# config.net
KiCad netlist of a schematic drawn in Altium Designer
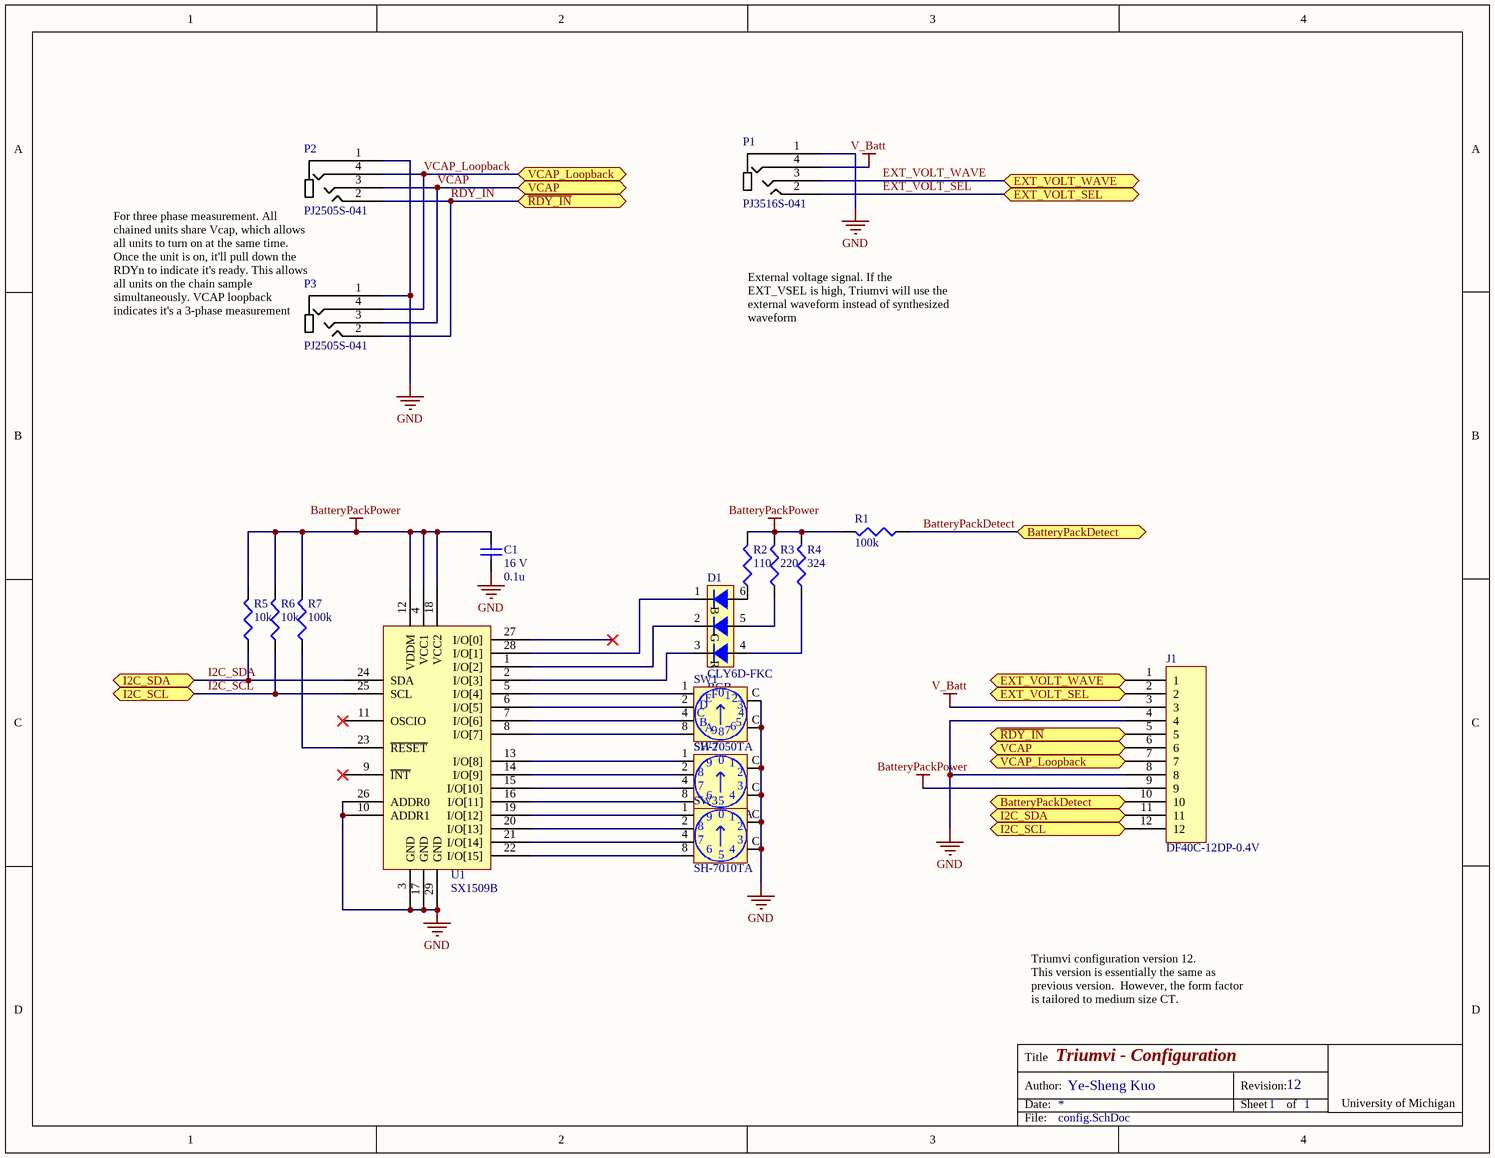
[diagram p0: config.SchDoc]

(export (version "E")
  (design (tool "Eeschema 10.0.6"))
  (components
    (comp (ref "C1")
      (value "0.1u")
      (footprint "0402")
      (description "0.10µF ±10% 16V Ceramic Capacitor X7R 0402")
      (fields
        (field (name "VOLTAGE RATED") "16 V")
        (field (name "TOLERANCE") "10%")
        (field (name "MANUFACTURER PART NUMBER") "GRM155R71C104KA88D")
      )
      (libsource (lib "capacitors") (part "GRM155R71C104KA88D"))
    )
    (comp (ref "D1")
      (value "CLY6D-FKC")
      (footprint "PLCC6")
      (fields
        (field (name "MANUFACTURER PART NUMBER") "CLY6D-FKC-CK1N1D1BB7D3D3")
        (field (name "MANUFACTURER") "CREE Inc")
        (field (name "ALTIUM_VALUE") "RGB")
      )
      (libsource (lib "LED") (part "CLY6D-FKC-CK1N1D1BB7D3D3"))
    )
    (comp (ref "J1")
      (value "DF40C-12DP-0.4V")
      (footprint "DF40C-12DP-0.4V")
      (description "Hirose BM20 Series, 0.4mm pitch, 12 pos, header")
      (libsource (lib "connectors") (part "DF40C-12DP-0.4V"))
    )
    (comp (ref "P1")
      (value "PJ3516S-041")
      (footprint "PJ3516S-041")
      (description "3.5 mm phone jack, 4 terminals")
      (libsource (lib "connectors") (part "PJ3516S-041"))
    )
    (comp (ref "P2")
      (value "PJ2505S-041")
      (footprint "PJ2505S-041")
      (description "2.5 mm phone jack, 4 terminals")
      (libsource (lib "connectors") (part "PJ2505S-041"))
    )
    (comp (ref "P3")
      (value "PJ2505S-041")
      (footprint "PJ2505S-041")
      (description "2.5 mm phone jack, 4 terminals")
      (libsource (lib "connectors") (part "PJ2505S-041"))
    )
    (comp (ref "R1")
      (value "100k")
      (footprint "0402")
      (description "RES SMD 100K OHM 1% 1/16W 0402")
      (fields (field (name "TOLERANCE") "1%") (field (name "POWER") "1/16 W"))
      (libsource (lib "resistors") (part "CRCW0402100KFKED"))
    )
    (comp (ref "R2")
      (value "110")
      (footprint "0402")
      (description "RES SMD 110 OHM 1% 1/16W 0402")
      (fields (field (name "TOLERANCE") "1%") (field (name "POWER") "1/16 W"))
      (libsource (lib "resistors") (part "CRCW0402110RFKED"))
    )
    (comp (ref "R3")
      (value "220")
      (footprint "0402")
      (description "RES SMD 220 OHM 1% 1/16W 0402")
      (fields (field (name "TOLERANCE") "1%") (field (name "POWER") "1/5 W"))
      (libsource (lib "resistors") (part "CRCW0402220RFKED"))
    )
    (comp (ref "R4")
      (value "324")
      (footprint "0402")
      (description "RES SMD 324 OHM 1% 1/16W 0402")
      (fields (field (name "TOLERANCE") "1%") (field (name "POWER") "1/16 W"))
      (libsource (lib "resistors") (part "CRCW0402324RFKED"))
    )
    (comp (ref "R5")
      (value "10k")
      (footprint "0402")
      (description "RES SMD 10K OHM 1% 1/16W 0402")
      (fields (field (name "TOLERANCE") "1%") (field (name "POWER") "1/16 W"))
      (libsource (lib "resistors") (part "CRCW040210K0FKED"))
    )
    (comp (ref "R6")
      (value "10k")
      (footprint "0402")
      (description "RES SMD 10K OHM 1% 1/16W 0402")
      (fields (field (name "TOLERANCE") "1%") (field (name "POWER") "1/16 W"))
      (libsource (lib "resistors") (part "CRCW040210K0FKED"))
    )
    (comp (ref "R7")
      (value "100k")
      (footprint "0402")
      (description "RES SMD 100K OHM 1% 1/16W 0402")
      (fields (field (name "TOLERANCE") "1%") (field (name "POWER") "1/16 W"))
      (libsource (lib "resistors") (part "CRCW0402100KFKED"))
    )
    (comp (ref "SW1")
      (value "SH-7050TA")
      (footprint "SH-7050A")
      (description "ROTARY CODED SWITCHES")
      (libsource (lib "switches") (part "SH-7050TA"))
    )
    (comp (ref "SW2")
      (value "SH-7010TA")
      (footprint "SH-7010A")
      (description "ROTARY CODED SWITCHES")
      (libsource (lib "switches") (part "SH-7010TA"))
    )
    (comp (ref "SW3")
      (value "SH-7010TA")
      (footprint "SH-7010A")
      (description "ROTARY CODED SWITCHES")
      (libsource (lib "switches") (part "SH-7010TA"))
    )
    (comp (ref "U1")
      (value "SX1509B")
      (footprint "QFN40P400X400X60_HS-29N")
      (description "Voltage Level Shifting GPIO  with LED Driver and Keypad Engine")
      (libsource (lib "io expander") (part "SX1509B"))
    )
  )
  (nets
    (net (code "1") (name "/BatteryPackDetect") (class "Default")
      (node (ref "J1") (pin "10") (pinfunction "10_10") (pintype "passive"))
      (node (ref "R1") (pin "2") (pintype "passive"))
    )
    (net (code "2") (name "/EXT_VOLT_SEL") (class "Default")
      (node (ref "J1") (pin "2") (pinfunction "2_2") (pintype "passive"))
      (node (ref "P1") (pin "2") (pinfunction "2_2") (pintype "passive"))
    )
    (net (code "3") (name "/EXT_VOLT_WAVE") (class "Default")
      (node (ref "J1") (pin "1") (pinfunction "1_1") (pintype "passive"))
      (node (ref "P1") (pin "3") (pinfunction "3_3") (pintype "passive"))
    )
    (net (code "4") (name "/I2C_SCL") (class "Default")
      (node (ref "J1") (pin "12") (pinfunction "12_12") (pintype "passive"))
      (node (ref "R6") (pin "2") (pintype "passive"))
      (node (ref "U1") (pin "25") (pinfunction "SCL_25") (pintype "passive"))
    )
    (net (code "5") (name "/I2C_SDA") (class "Default")
      (node (ref "J1") (pin "11") (pinfunction "11_11") (pintype "passive"))
      (node (ref "R5") (pin "2") (pintype "passive"))
      (node (ref "U1") (pin "24") (pinfunction "SDA_24") (pintype "passive"))
    )
    (net (code "6") (name "/VCAP") (class "Default")
      (node (ref "J1") (pin "6") (pinfunction "6_6") (pintype "passive"))
      (node (ref "P2") (pin "3") (pinfunction "3_3") (pintype "passive"))
      (node (ref "P3") (pin "3") (pinfunction "3_3") (pintype "passive"))
    )
    (net (code "7") (name "/VCAP_Loopback") (class "Default")
      (node (ref "J1") (pin "7") (pinfunction "7_7") (pintype "passive"))
      (node (ref "P2") (pin "4") (pinfunction "4_4") (pintype "passive"))
      (node (ref "P3") (pin "4") (pinfunction "4_4") (pintype "passive"))
    )
    (net (code "8") (name "/~{RDY_IN}") (class "Default")
      (node (ref "J1") (pin "5") (pinfunction "5_5") (pintype "passive"))
      (node (ref "P2") (pin "2") (pinfunction "2_2") (pintype "passive"))
      (node (ref "P3") (pin "2") (pinfunction "2_2") (pintype "passive"))
    )
    (net (code "9") (name "BatteryPackPower") (class "Default")
      (node (ref "C1") (pin "1") (pintype "passive"))
      (node (ref "J1") (pin "9") (pinfunction "9_9") (pintype "passive"))
      (node (ref "R1") (pin "1") (pintype "passive"))
      (node (ref "R2") (pin "1") (pintype "passive"))
      (node (ref "R3") (pin "1") (pintype "passive"))
      (node (ref "R4") (pin "1") (pintype "passive"))
      (node (ref "R5") (pin "1") (pintype "passive"))
      (node (ref "R6") (pin "1") (pintype "passive"))
      (node (ref "R7") (pin "1") (pintype "passive"))
      (node (ref "U1") (pin "12") (pinfunction "VDDM_12") (pintype "passive"))
      (node (ref "U1") (pin "18") (pinfunction "VCC2_18") (pintype "passive"))
      (node (ref "U1") (pin "4") (pinfunction "VCC1_4") (pintype "passive"))
    )
    (net (code "10") (name "GND") (class "Default")
      (node (ref "C1") (pin "2") (pintype "passive"))
      (node (ref "J1") (pin "4") (pinfunction "4_4") (pintype "passive"))
      (node (ref "J1") (pin "8") (pinfunction "8_8") (pintype "passive"))
      (node (ref "P1") (pin "1") (pinfunction "1_1") (pintype "passive"))
      (node (ref "P2") (pin "1") (pinfunction "1_1") (pintype "passive"))
      (node (ref "P3") (pin "1") (pinfunction "1_1") (pintype "passive"))
      (node (ref "SW1") (pin "C") (pinfunction "C_C") (pintype "passive"))
      (node (ref "SW2") (pin "C") (pinfunction "C_C") (pintype "passive"))
      (node (ref "SW3") (pin "C") (pinfunction "C_C") (pintype "passive"))
      (node (ref "U1") (pin "10") (pinfunction "ADDR1_10") (pintype "passive"))
      (node (ref "U1") (pin "17") (pinfunction "GND_17") (pintype "passive"))
      (node (ref "U1") (pin "26") (pinfunction "ADDR0_26") (pintype "passive"))
      (node (ref "U1") (pin "29") (pinfunction "GND_29") (pintype "passive"))
      (node (ref "U1") (pin "3") (pinfunction "GND_3") (pintype "passive"))
    )
    (net (code "11") (name "Net-(D1-Pad4)") (class "Default")
      (node (ref "D1") (pin "4") (pinfunction "4_4") (pintype "passive"))
      (node (ref "R4") (pin "2") (pintype "passive"))
    )
    (net (code "12") (name "Net-(D1-Pad5)") (class "Default")
      (node (ref "D1") (pin "5") (pinfunction "5_5") (pintype "passive"))
      (node (ref "R3") (pin "2") (pintype "passive"))
    )
    (net (code "13") (name "Net-(D1-Pad6)") (class "Default")
      (node (ref "D1") (pin "6") (pinfunction "6_6") (pintype "passive"))
      (node (ref "R2") (pin "2") (pintype "passive"))
    )
    (net (code "14") (name "Net-(U1-I{slash}O[1])") (class "Default")
      (node (ref "D1") (pin "1") (pintype "passive"))
      (node (ref "U1") (pin "28") (pinfunction "I/O[1]_28") (pintype "passive"))
    )
    (net (code "15") (name "Net-(U1-I{slash}O[2])") (class "Default")
      (node (ref "D1") (pin "2") (pintype "passive"))
      (node (ref "U1") (pin "1") (pinfunction "I/O[2]_1") (pintype "passive"))
    )
    (net (code "16") (name "Net-(U1-I{slash}O[3])") (class "Default")
      (node (ref "D1") (pin "3") (pinfunction "3_3") (pintype "passive"))
      (node (ref "U1") (pin "2") (pinfunction "I/O[3]_2") (pintype "passive"))
    )
    (net (code "17") (name "Net-(U1-I{slash}O[4])") (class "Default")
      (node (ref "SW1") (pin "1") (pinfunction "1_1") (pintype "passive"))
      (node (ref "U1") (pin "5") (pinfunction "I/O[4]_5") (pintype "passive"))
    )
    (net (code "18") (name "Net-(U1-I{slash}O[5])") (class "Default")
      (node (ref "SW1") (pin "2") (pinfunction "2_2") (pintype "passive"))
      (node (ref "U1") (pin "6") (pinfunction "I/O[5]_6") (pintype "passive"))
    )
    (net (code "19") (name "Net-(U1-I{slash}O[6])") (class "Default")
      (node (ref "SW1") (pin "4") (pinfunction "4_4") (pintype "passive"))
      (node (ref "U1") (pin "7") (pinfunction "I/O[6]_7") (pintype "passive"))
    )
    (net (code "20") (name "Net-(U1-I{slash}O[7])") (class "Default")
      (node (ref "SW1") (pin "8") (pinfunction "8_8") (pintype "passive"))
      (node (ref "U1") (pin "8") (pinfunction "I/O[7]_8") (pintype "passive"))
    )
    (net (code "21") (name "Net-(U1-I{slash}O[8])") (class "Default")
      (node (ref "SW2") (pin "1") (pinfunction "1_1") (pintype "passive"))
      (node (ref "U1") (pin "13") (pinfunction "I/O[8]_13") (pintype "passive"))
    )
    (net (code "22") (name "Net-(U1-I{slash}O[9])") (class "Default")
      (node (ref "SW2") (pin "2") (pinfunction "2_2") (pintype "passive"))
      (node (ref "U1") (pin "14") (pinfunction "I/O[9]_14") (pintype "passive"))
    )
    (net (code "23") (name "Net-(U1-I{slash}O[10])") (class "Default")
      (node (ref "SW2") (pin "4") (pinfunction "4_4") (pintype "passive"))
      (node (ref "U1") (pin "15") (pinfunction "I/O[10]_15") (pintype "passive"))
    )
    (net (code "24") (name "Net-(U1-I{slash}O[11])") (class "Default")
      (node (ref "SW2") (pin "8") (pinfunction "8_8") (pintype "passive"))
      (node (ref "U1") (pin "16") (pinfunction "I/O[11]_16") (pintype "passive"))
    )
    (net (code "25") (name "Net-(U1-I{slash}O[12])") (class "Default")
      (node (ref "SW3") (pin "1") (pinfunction "1_1") (pintype "passive"))
      (node (ref "U1") (pin "19") (pinfunction "I/O[12]_19") (pintype "passive"))
    )
    (net (code "26") (name "Net-(U1-I{slash}O[13])") (class "Default")
      (node (ref "SW3") (pin "2") (pinfunction "2_2") (pintype "passive"))
      (node (ref "U1") (pin "20") (pinfunction "I/O[13]_20") (pintype "passive"))
    )
    (net (code "27") (name "Net-(U1-I{slash}O[14])") (class "Default")
      (node (ref "SW3") (pin "4") (pinfunction "4_4") (pintype "passive"))
      (node (ref "U1") (pin "21") (pinfunction "I/O[14]_21") (pintype "passive"))
    )
    (net (code "28") (name "Net-(U1-I{slash}O[15])") (class "Default")
      (node (ref "SW3") (pin "8") (pinfunction "8_8") (pintype "passive"))
      (node (ref "U1") (pin "22") (pinfunction "I/O[15]_22") (pintype "passive"))
    )
    (net (code "29") (name "Net-(U1-~{RESET})") (class "Default")
      (node (ref "R7") (pin "2") (pintype "passive"))
      (node (ref "U1") (pin "23") (pinfunction "~{RESET}_23") (pintype "passive"))
    )
    (net (code "30") (name "V_Batt") (class "Default")
      (node (ref "J1") (pin "3") (pinfunction "3_3") (pintype "passive"))
      (node (ref "P1") (pin "4") (pinfunction "4_4") (pintype "passive"))
    )
    (net (code "31") (name "unconnected-(U1-I{slash}O[0]-Pad27)") (class "Default")
      (node (ref "U1") (pin "27") (pinfunction "I/O[0]_27") (pintype "passive+no_connect"))
    )
    (net (code "32") (name "unconnected-(U1-OSCIO-Pad11)") (class "Default")
      (node (ref "U1") (pin "11") (pinfunction "OSCIO_11") (pintype "passive+no_connect"))
    )
    (net (code "33") (name "unconnected-(U1-~{INT}-Pad9)") (class "Default")
      (node (ref "U1") (pin "9") (pinfunction "~{INT}_9") (pintype "passive+no_connect"))
    )
  )
)
